# MGMEZZ04.net
KiCad netlist of a schematic drawn in Altium Designer
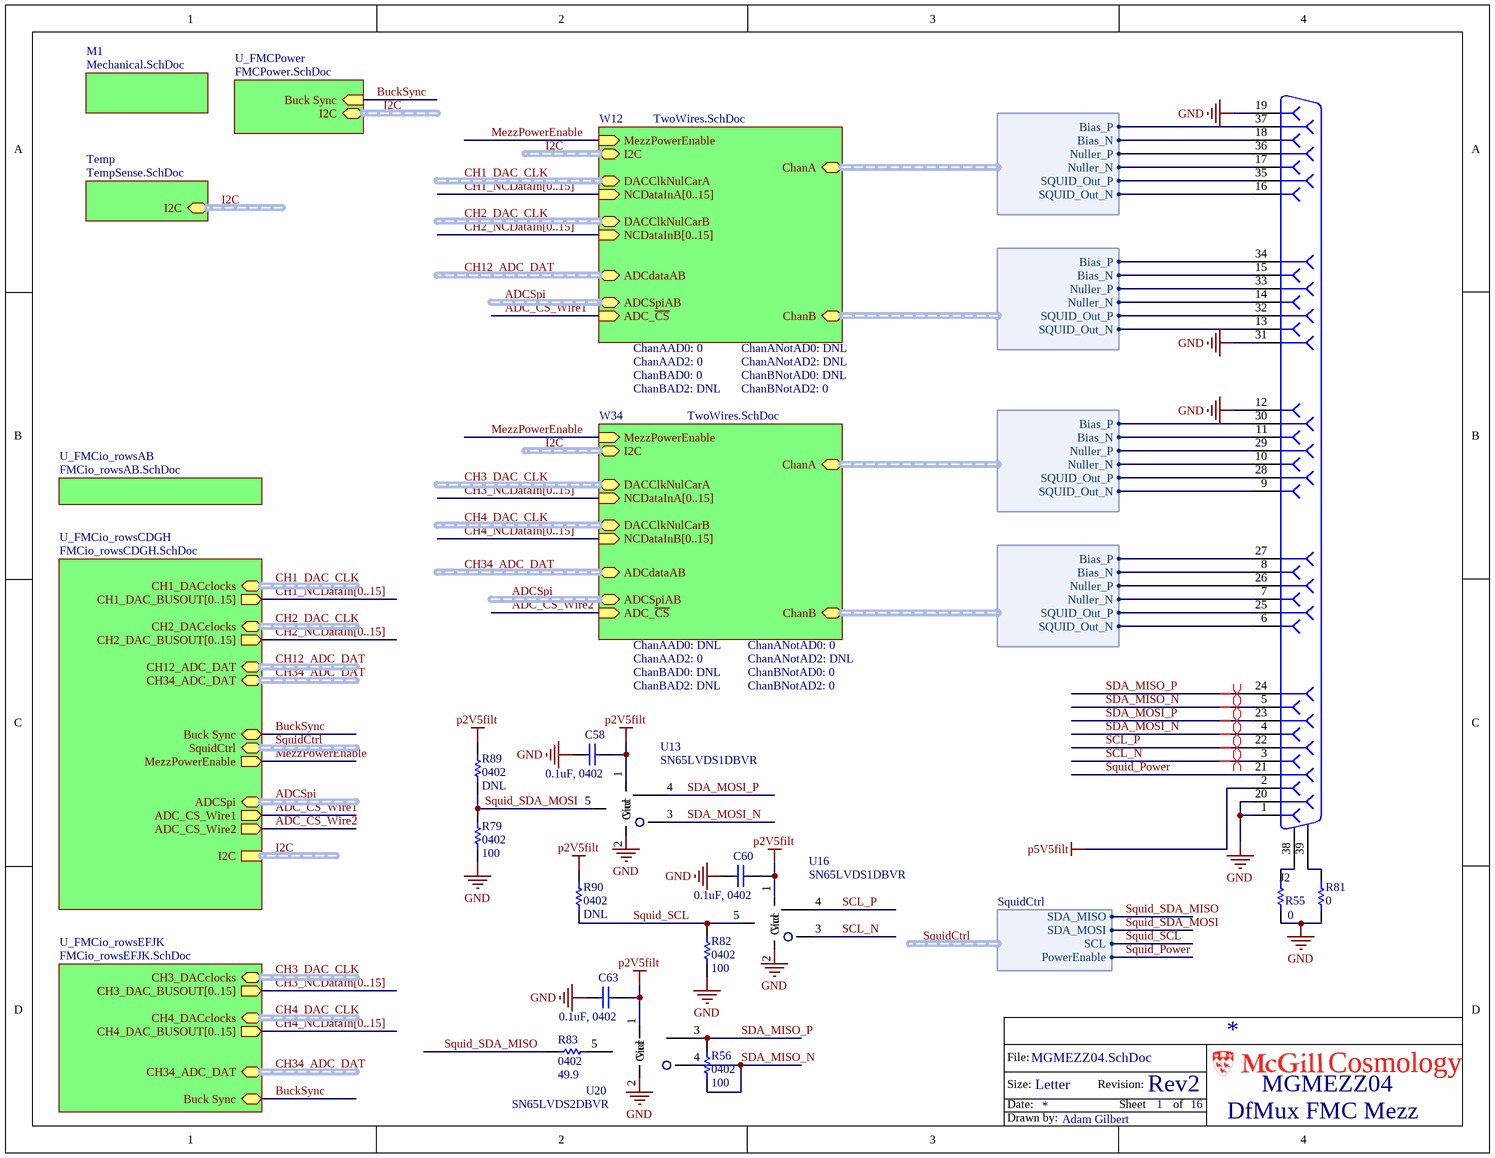
[diagram p0: MGMEZZ04.SchDoc]

(export (version "E")
  (design (tool "Eeschema 10.0.6"))
  (components
    (comp (ref "C58")
      (value "0.1uF, 0402")
      (footprint "0402")
      (description "Capacitor, Ceramic, 0402")
      (fields (field (name "MANUFACTURER") "TDK Corporation"))
      (libsource (lib "MGMEZZ04") (part "CAP 0603"))
    )
    (comp (ref "C60")
      (value "0.1uF, 0402")
      (footprint "0402")
      (description "Capacitor, Ceramic, 0402")
      (fields (field (name "MANUFACTURER") "TDK Corporation"))
      (libsource (lib "MGMEZZ04") (part "CAP 0603"))
    )
    (comp (ref "C63")
      (value "0.1uF, 0402")
      (footprint "0402")
      (description "Capacitor, Ceramic, 0402")
      (fields (field (name "MANUFACTURER") "TDK Corporation"))
      (libsource (lib "MGMEZZ04") (part "CAP 0603"))
    )
    (comp (ref "J2")
      (value "DB37F_Resize")
      (footprint "DSUB37-F")
      (description "DB37F")
      (fields (field (name "MANUFACTURER") "Norcomp Inc."))
      (libsource (lib "MGMEZZ04") (part "DB37F_Resize"))
    )
    (comp (ref "R55")
      (value "0")
      (footprint "0603")
      (description "RES 0603")
      (fields (field (name "MANUFACTURER") "e.g CRCW0603 series"))
      (libsource (lib "MiniSquidCtrl") (part "RES 0603"))
    )
    (comp (ref "R56")
      (value "100")
      (footprint "0402")
      (description "Resistor")
      (fields (field (name "MANUFACTURER") "Generic"))
      (libsource (lib "MGMEZZ04") (part "RES 0402"))
    )
    (comp (ref "R79")
      (value "100")
      (footprint "0402")
      (description "Resistor")
      (fields (field (name "MANUFACTURER") "Generic"))
      (libsource (lib "MGMEZZ04") (part "RES 0402"))
    )
    (comp (ref "R81")
      (value "0")
      (footprint "0603")
      (description "RES 0603")
      (fields (field (name "MANUFACTURER") "e.g CRCW0603 series"))
      (libsource (lib "MiniSquidCtrl") (part "RES 0603"))
    )
    (comp (ref "R82")
      (value "100")
      (footprint "0402")
      (description "Resistor")
      (fields (field (name "MANUFACTURER") "Generic"))
      (libsource (lib "MGMEZZ04") (part "RES 0402"))
    )
    (comp (ref "R83")
      (value "49.9")
      (footprint "0402")
      (description "Resistor")
      (fields (field (name "MANUFACTURER") "Generic"))
      (libsource (lib "MGMEZZ04") (part "RES 0402"))
    )
    (comp (ref "R89")
      (value "DNL")
      (footprint "0402")
      (description "Resistor")
      (fields (field (name "MANUFACTURER") "Generic"))
      (libsource (lib "MGMEZZ04") (part "RES 0402"))
    )
    (comp (ref "R90")
      (value "DNL")
      (footprint "0402")
      (description "Resistor")
      (fields (field (name "MANUFACTURER") "Generic"))
      (libsource (lib "MGMEZZ04") (part "RES 0402"))
    )
    (comp (ref "U13")
      (value "SN65LVDS1DBVR")
      (footprint "SOT23-5")
      (description "IC HIGH DIFF LINE DRIVER SOT23-5")
      (fields (field (name "MANUFACTURER") "Texas Instruments"))
      (libsource (lib "MGMEZZ04") (part "SN65LVDS1DBVR"))
    )
    (comp (ref "U16")
      (value "SN65LVDS1DBVR")
      (footprint "SOT23-5")
      (description "IC HIGH DIFF LINE DRIVER SOT23-5")
      (fields (field (name "MANUFACTURER") "Texas Instruments"))
      (libsource (lib "MGMEZZ04") (part "SN65LVDS1DBVR"))
    )
    (comp (ref "U20")
      (value "SN65LVDS2DBVR")
      (footprint "SOT23-5")
      (description "IC DIF LINE DRVR/RCVR HS SOT23-5")
      (fields (field (name "MANUFACTURER") "Texas Instruments"))
      (libsource (lib "MGMEZZ04") (part "SN65LVDS2DBVR"))
    )
  )
  (nets
    (net (code "84") (name "/SCL_N") (class "Default")
      (node (ref "J2") (pin "3") (pinfunction "3_3") (pintype "passive"))
      (node (ref "U16") (pin "3") (pinfunction "A_3") (pintype "passive"))
    )
    (net (code "85") (name "/SCL_P") (class "Default")
      (node (ref "J2") (pin "22") (pinfunction "22_22") (pintype "passive"))
      (node (ref "U16") (pin "4") (pinfunction "B_4") (pintype "passive"))
    )
    (net (code "86") (name "/SDA_MISO_N") (class "Default")
      (node (ref "J2") (pin "5") (pinfunction "5_5") (pintype "passive"))
      (node (ref "R56") (pin "2") (pinfunction "2_2") (pintype "passive"))
      (node (ref "U20") (pin "4") (pinfunction "B_4") (pintype "passive"))
    )
    (net (code "87") (name "/SDA_MISO_P") (class "Default")
      (node (ref "J2") (pin "24") (pinfunction "24_24") (pintype "passive"))
      (node (ref "R56") (pin "1") (pinfunction "1_1") (pintype "passive"))
      (node (ref "U20") (pin "3") (pinfunction "A_3") (pintype "passive"))
    )
    (net (code "88") (name "/SDA_MOSI_N") (class "Default")
      (node (ref "J2") (pin "4") (pinfunction "4_4") (pintype "passive"))
      (node (ref "U13") (pin "3") (pinfunction "A_3") (pintype "passive"))
    )
    (net (code "89") (name "/SDA_MOSI_P") (class "Default")
      (node (ref "J2") (pin "23") (pinfunction "23_23") (pintype "passive"))
      (node (ref "U13") (pin "4") (pinfunction "B_4") (pintype "passive"))
    )
    (net (code "91") (name "/Squid_Power") (class "Default")
      (node (ref "J2") (pin "21") (pinfunction "21_21") (pintype "passive"))
    )
    (net (code "92") (name "/Squid_SCL") (class "Default")
      (node (ref "R82") (pin "2") (pinfunction "2_2") (pintype "passive"))
      (node (ref "R90") (pin "1") (pinfunction "1_1") (pintype "passive"))
      (node (ref "U16") (pin "5") (pinfunction "R_5") (pintype "passive"))
    )
    (net (code "93") (name "/Squid_SDA_MISO") (class "Default")
      (node (ref "R83") (pin "2") (pinfunction "2_2") (pintype "passive"))
    )
    (net (code "94") (name "/Squid_SDA_MOSI") (class "Default")
      (node (ref "R79") (pin "2") (pinfunction "2_2") (pintype "passive"))
      (node (ref "R89") (pin "1") (pinfunction "1_1") (pintype "passive"))
      (node (ref "U13") (pin "5") (pinfunction "R_5") (pintype "passive"))
    )
    (net (code "105") (name "GND") (class "Default")
      (node (ref "C58") (pin "2") (pinfunction "2_2") (pintype "passive"))
      (node (ref "C60") (pin "2") (pinfunction "2_2") (pintype "passive"))
      (node (ref "C63") (pin "2") (pinfunction "2_2") (pintype "passive"))
      (node (ref "J2") (pin "1") (pinfunction "1_1") (pintype "passive"))
      (node (ref "J2") (pin "12") (pinfunction "12_12") (pintype "passive"))
      (node (ref "J2") (pin "19") (pinfunction "19_19") (pintype "passive"))
      (node (ref "J2") (pin "20") (pinfunction "20_20") (pintype "passive"))
      (node (ref "J2") (pin "31") (pinfunction "31_31") (pintype "passive"))
      (node (ref "R55") (pin "1") (pinfunction "1_1") (pintype "passive"))
      (node (ref "R79") (pin "1") (pinfunction "1_1") (pintype "passive"))
      (node (ref "R81") (pin "2") (pinfunction "2_2") (pintype "passive"))
      (node (ref "R82") (pin "1") (pinfunction "1_1") (pintype "passive"))
      (node (ref "U13") (pin "2") (pinfunction "Gnd_2") (pintype "passive"))
      (node (ref "U16") (pin "2") (pinfunction "Gnd_2") (pintype "passive"))
      (node (ref "U20") (pin "2") (pinfunction "Gnd_2") (pintype "passive"))
    )
    (net (code "106") (name "Net-(J2-MH1)") (class "Default")
      (node (ref "J2") (pin "38") (pinfunction "MH1_38") (pintype "passive"))
      (node (ref "R55") (pin "2") (pinfunction "2_2") (pintype "passive"))
    )
    (net (code "107") (name "Net-(J2-MH2)") (class "Default")
      (node (ref "J2") (pin "39") (pinfunction "MH2_39") (pintype "passive"))
      (node (ref "R81") (pin "1") (pinfunction "1_1") (pintype "passive"))
    )
    (net (code "108") (name "Net-(U20-R)") (class "Default")
      (node (ref "R83") (pin "1") (pinfunction "1_1") (pintype "passive"))
      (node (ref "U20") (pin "5") (pinfunction "R_5") (pintype "passive"))
    )
    (net (code "109") (name "p2V5filt") (class "Default")
      (node (ref "C58") (pin "1") (pinfunction "1_1") (pintype "passive"))
      (node (ref "C60") (pin "1") (pinfunction "1_1") (pintype "passive"))
      (node (ref "C63") (pin "1") (pinfunction "1_1") (pintype "passive"))
      (node (ref "R89") (pin "2") (pinfunction "2_2") (pintype "passive"))
      (node (ref "R90") (pin "2") (pinfunction "2_2") (pintype "passive"))
      (node (ref "U13") (pin "1") (pinfunction "Vcc_1") (pintype "passive"))
      (node (ref "U16") (pin "1") (pinfunction "Vcc_1") (pintype "passive"))
      (node (ref "U20") (pin "1") (pinfunction "Vcc_1") (pintype "passive"))
    )
    (net (code "110") (name "p5V5filt") (class "Default")
      (node (ref "J2") (pin "2") (pinfunction "2_2") (pintype "passive"))
    )
    (net (code "111") (name "unconnected-(J2-Pad6)") (class "Default")
      (node (ref "J2") (pin "6") (pinfunction "6_6") (pintype "passive"))
    )
    (net (code "112") (name "unconnected-(J2-Pad7)") (class "Default")
      (node (ref "J2") (pin "7") (pinfunction "7_7") (pintype "passive"))
    )
    (net (code "113") (name "unconnected-(J2-Pad8)") (class "Default")
      (node (ref "J2") (pin "8") (pinfunction "8_8") (pintype "passive"))
    )
    (net (code "114") (name "unconnected-(J2-Pad9)") (class "Default")
      (node (ref "J2") (pin "9") (pinfunction "9_9") (pintype "passive"))
    )
    (net (code "115") (name "unconnected-(J2-Pad10)") (class "Default")
      (node (ref "J2") (pin "10") (pinfunction "10_10") (pintype "passive"))
    )
    (net (code "116") (name "unconnected-(J2-Pad11)") (class "Default")
      (node (ref "J2") (pin "11") (pinfunction "11_11") (pintype "passive"))
    )
    (net (code "117") (name "unconnected-(J2-Pad13)") (class "Default")
      (node (ref "J2") (pin "13") (pinfunction "13_13") (pintype "passive"))
    )
    (net (code "118") (name "unconnected-(J2-Pad14)") (class "Default")
      (node (ref "J2") (pin "14") (pinfunction "14_14") (pintype "passive"))
    )
    (net (code "119") (name "unconnected-(J2-Pad15)") (class "Default")
      (node (ref "J2") (pin "15") (pinfunction "15_15") (pintype "passive"))
    )
    (net (code "120") (name "unconnected-(J2-Pad16)") (class "Default")
      (node (ref "J2") (pin "16") (pinfunction "16_16") (pintype "passive"))
    )
    (net (code "121") (name "unconnected-(J2-Pad17)") (class "Default")
      (node (ref "J2") (pin "17") (pinfunction "17_17") (pintype "passive"))
    )
    (net (code "122") (name "unconnected-(J2-Pad18)") (class "Default")
      (node (ref "J2") (pin "18") (pinfunction "18_18") (pintype "passive"))
    )
    (net (code "123") (name "unconnected-(J2-Pad25)") (class "Default")
      (node (ref "J2") (pin "25") (pinfunction "25_25") (pintype "passive"))
    )
    (net (code "124") (name "unconnected-(J2-Pad26)") (class "Default")
      (node (ref "J2") (pin "26") (pinfunction "26_26") (pintype "passive"))
    )
    (net (code "125") (name "unconnected-(J2-Pad27)") (class "Default")
      (node (ref "J2") (pin "27") (pinfunction "27_27") (pintype "passive"))
    )
    (net (code "126") (name "unconnected-(J2-Pad28)") (class "Default")
      (node (ref "J2") (pin "28") (pinfunction "28_28") (pintype "passive"))
    )
    (net (code "127") (name "unconnected-(J2-Pad29)") (class "Default")
      (node (ref "J2") (pin "29") (pinfunction "29_29") (pintype "passive"))
    )
    (net (code "128") (name "unconnected-(J2-Pad30)") (class "Default")
      (node (ref "J2") (pin "30") (pinfunction "30_30") (pintype "passive"))
    )
    (net (code "129") (name "unconnected-(J2-Pad32)") (class "Default")
      (node (ref "J2") (pin "32") (pinfunction "32_32") (pintype "passive"))
    )
    (net (code "130") (name "unconnected-(J2-Pad33)") (class "Default")
      (node (ref "J2") (pin "33") (pinfunction "33_33") (pintype "passive"))
    )
    (net (code "131") (name "unconnected-(J2-Pad34)") (class "Default")
      (node (ref "J2") (pin "34") (pinfunction "34_34") (pintype "passive"))
    )
    (net (code "132") (name "unconnected-(J2-Pad35)") (class "Default")
      (node (ref "J2") (pin "35") (pinfunction "35_35") (pintype "passive"))
    )
    (net (code "133") (name "unconnected-(J2-Pad36)") (class "Default")
      (node (ref "J2") (pin "36") (pinfunction "36_36") (pintype "passive"))
    )
    (net (code "134") (name "unconnected-(J2-Pad37)") (class "Default")
      (node (ref "J2") (pin "37") (pinfunction "37_37") (pintype "passive"))
    )
  )
)
